# SCH_hackercard.net
KiCad netlist of a schematic drawn in EasyEDA
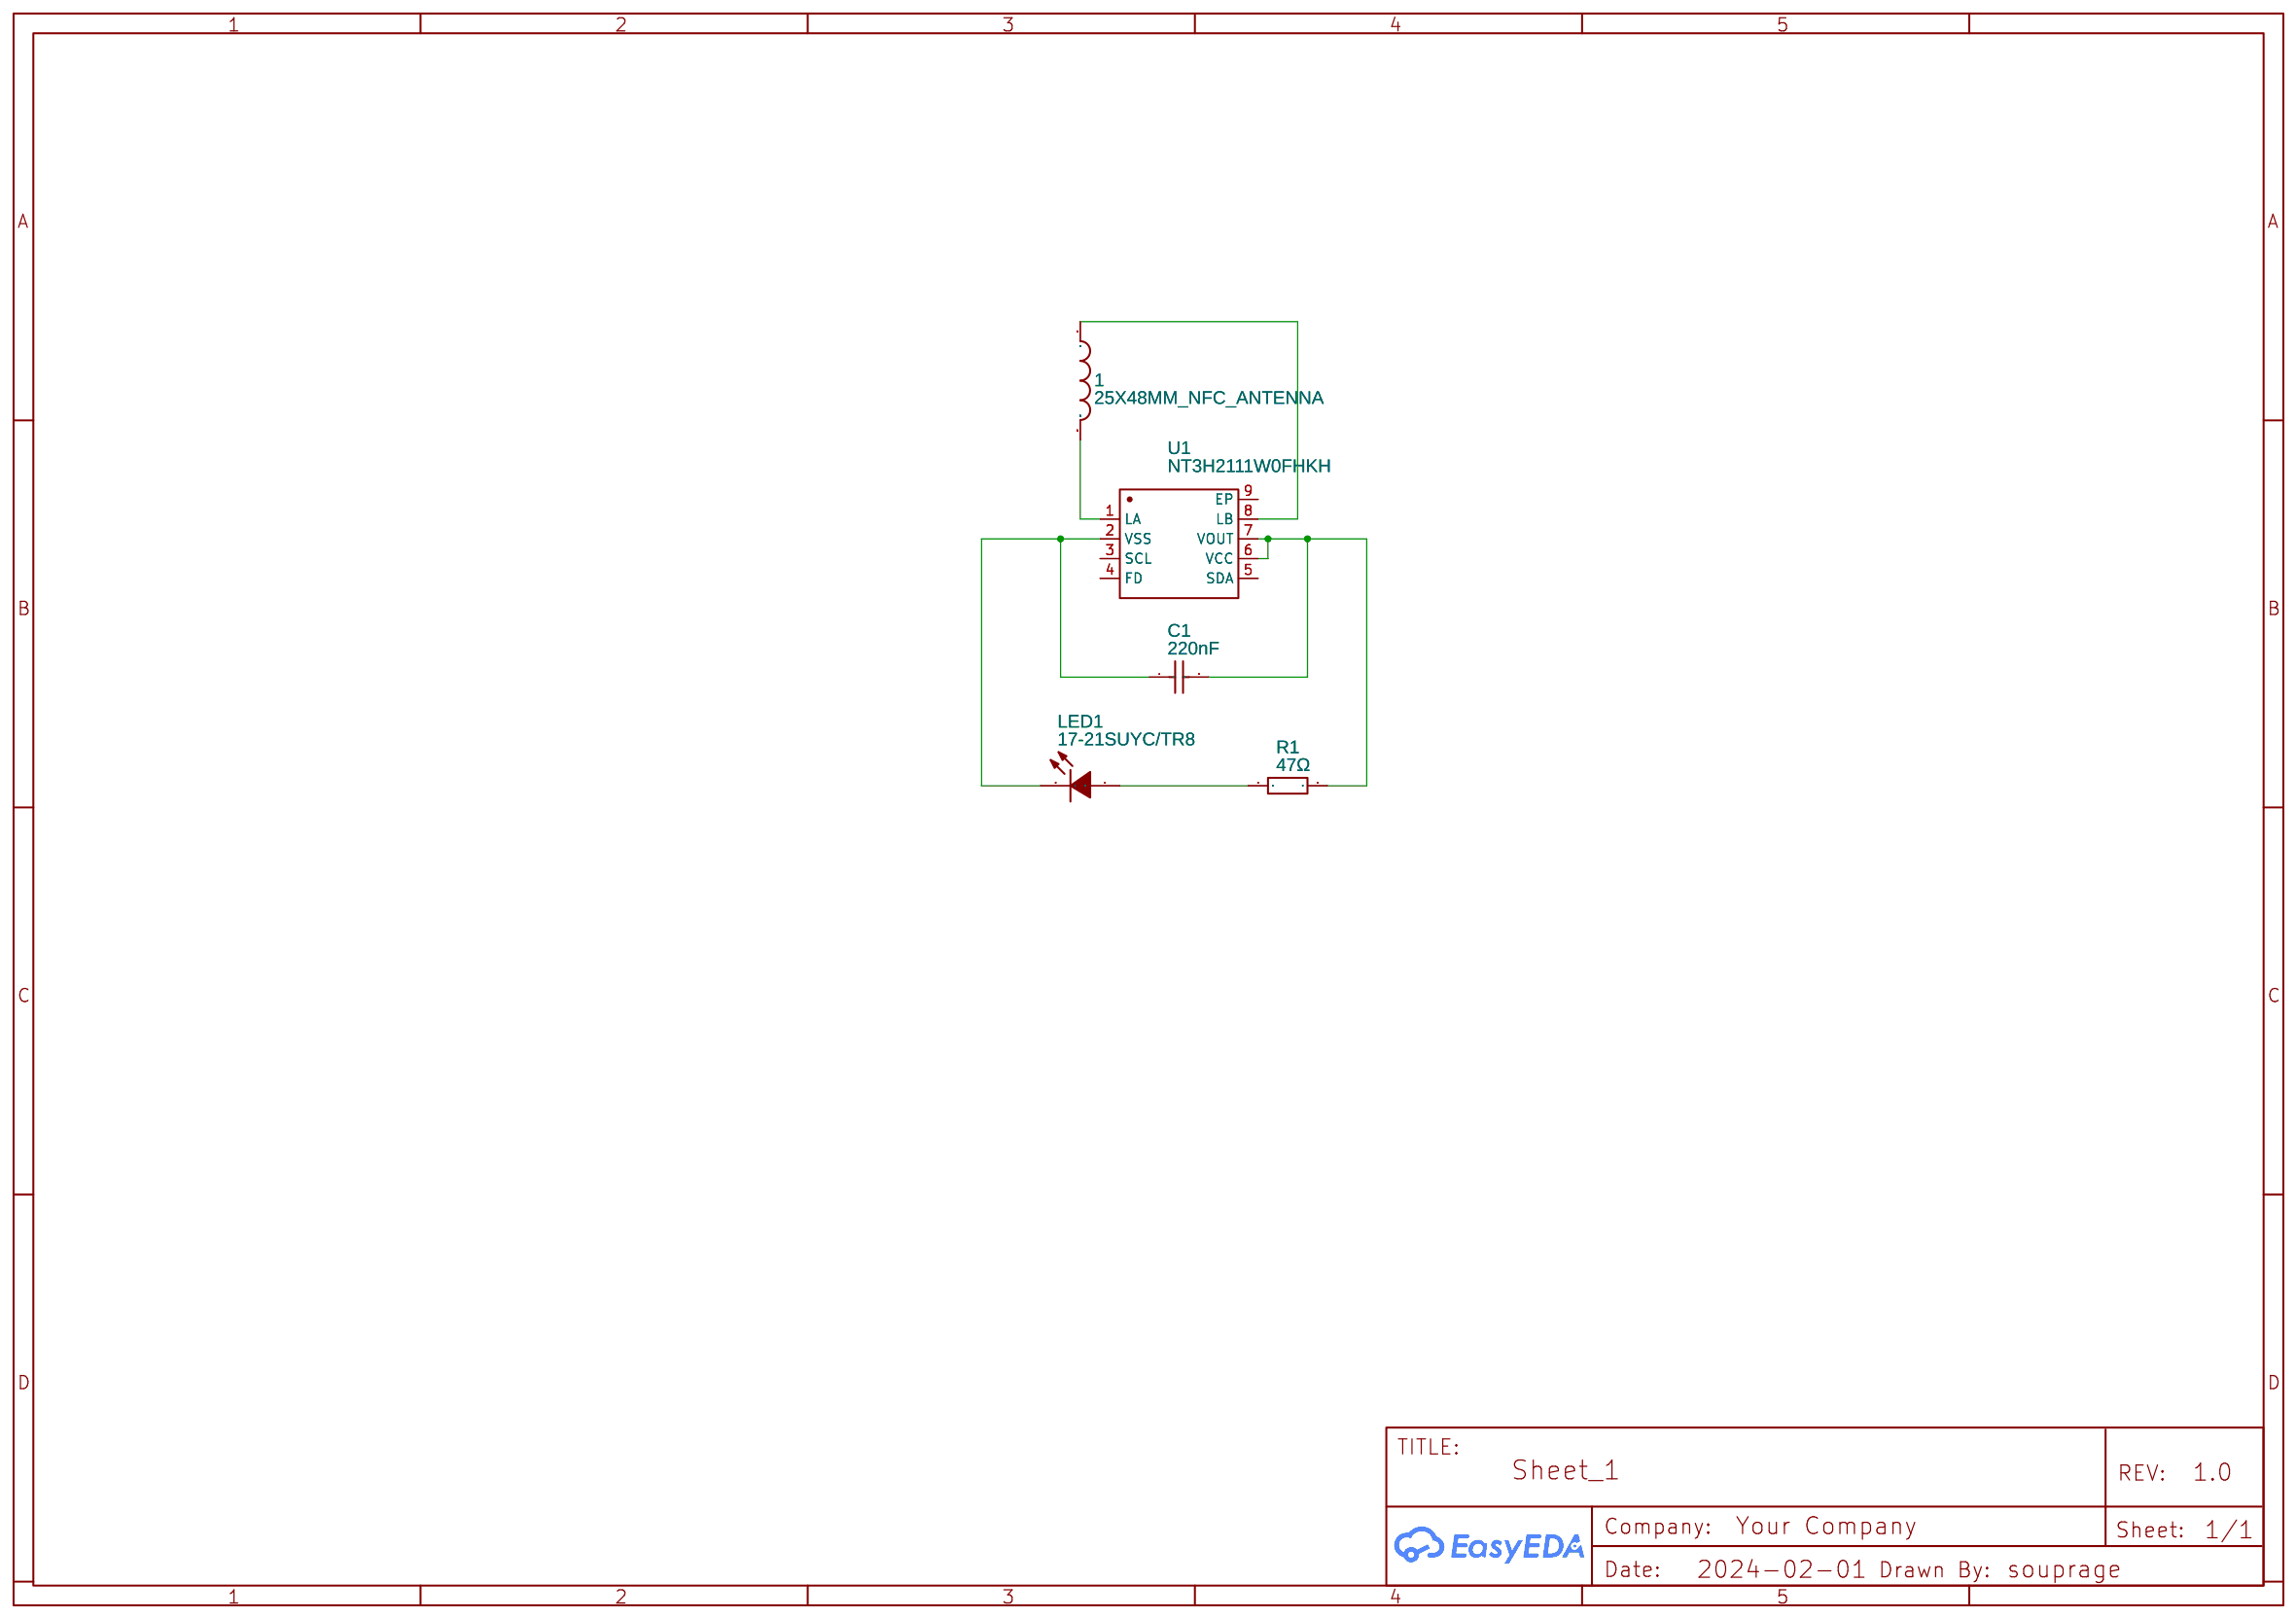
[diagram p0: schematic sheet]

(export (version "E")
  (design (tool "Eeschema 10.0.6"))
  (components
    (comp (ref "1") (value "25X48MM_NFC_ANTENNA") (libsource (lib "") (part "25X48MM_NFC_ANTENNA")))
    (comp (ref "C1")
      (value "220nF")
      (fields
        (field (name "Manufacturer Part") "CL10B224KA8NNNC")
        (field (name "Manufacturer") "SAMSUNG(三星)")
      )
      (libsource (lib "") (part "CL10B224KA8NNNC"))
    )
    (comp (ref "LED1")
      (value "17-21SUYC/TR8")
      (fields (field (name "Manufacturer Part") "KT-0805黄灯") (field (name "Manufacturer") "KENTO"))
      (libsource (lib "") (part "17-21SUYC/TR8"))
    )
    (comp (ref "R1")
      (value "47Ω")
      (fields
        (field (name "Manufacturer Part") "0603WAF470JT5E")
        (field (name "Manufacturer") "UNI-ROYAL(厚声)")
      )
      (libsource (lib "") (part "0603WAF470JT5E"))
    )
    (comp (ref "U1")
      (value "NT3H2111W0FHKH")
      (fields (field (name "Manufacturer") "NXP(恩智浦)"))
      (libsource (lib "") (part "NT3H2111W0FHKH"))
    )
  )
  (nets
    (net (code "1") (name "Net-(LED1-+)") (class "Default")
      (node (ref "LED1") (pin "1") (pinfunction "+_1") (pintype "unspecified"))
      (node (ref "R1") (pin "1") (pinfunction "1_1") (pintype "input"))
    )
    (net (code "2") (name "Net-(LED1--)") (class "Default")
      (node (ref "C1") (pin "1") (pinfunction "1_1") (pintype "input"))
      (node (ref "LED1") (pin "2") (pinfunction "-_2") (pintype "unspecified"))
      (node (ref "U1") (pin "2") (pinfunction "VSS_2") (pintype "unspecified"))
    )
    (net (code "3") (name "Net-(U1-LA)") (class "Default")
      (node (ref "1") (pin "P$2") (pinfunction "P$2_P$2") (pintype "bidirectional"))
      (node (ref "U1") (pin "1") (pinfunction "LA_1") (pintype "unspecified"))
    )
    (net (code "4") (name "Net-(U1-LB)") (class "Default")
      (node (ref "1") (pin "P$1") (pinfunction "P$1_P$1") (pintype "bidirectional"))
      (node (ref "U1") (pin "8") (pinfunction "LB_8") (pintype "unspecified"))
    )
    (net (code "5") (name "Net-(U1-VCC)") (class "Default")
      (node (ref "C1") (pin "2") (pinfunction "2_2") (pintype "input"))
      (node (ref "R1") (pin "2") (pinfunction "2_2") (pintype "input"))
      (node (ref "U1") (pin "6") (pinfunction "VCC_6") (pintype "unspecified"))
      (node (ref "U1") (pin "7") (pinfunction "VOUT_7") (pintype "unspecified"))
    )
    (net (code "6") (name "unconnected-(U1-EP-Pad9)") (class "Default")
      (node (ref "U1") (pin "9") (pinfunction "EP_9") (pintype "unspecified"))
    )
    (net (code "7") (name "unconnected-(U1-FD-Pad4)") (class "Default")
      (node (ref "U1") (pin "4") (pinfunction "FD_4") (pintype "unspecified"))
    )
    (net (code "8") (name "unconnected-(U1-SCL-Pad3)") (class "Default")
      (node (ref "U1") (pin "3") (pinfunction "SCL_3") (pintype "unspecified"))
    )
    (net (code "9") (name "unconnected-(U1-SDA-Pad5)") (class "Default")
      (node (ref "U1") (pin "5") (pinfunction "SDA_5") (pintype "unspecified"))
    )
  )
)
